# ArduinoMiniPro_Breakout.net
KiCad netlist of a schematic drawn in EAGLE
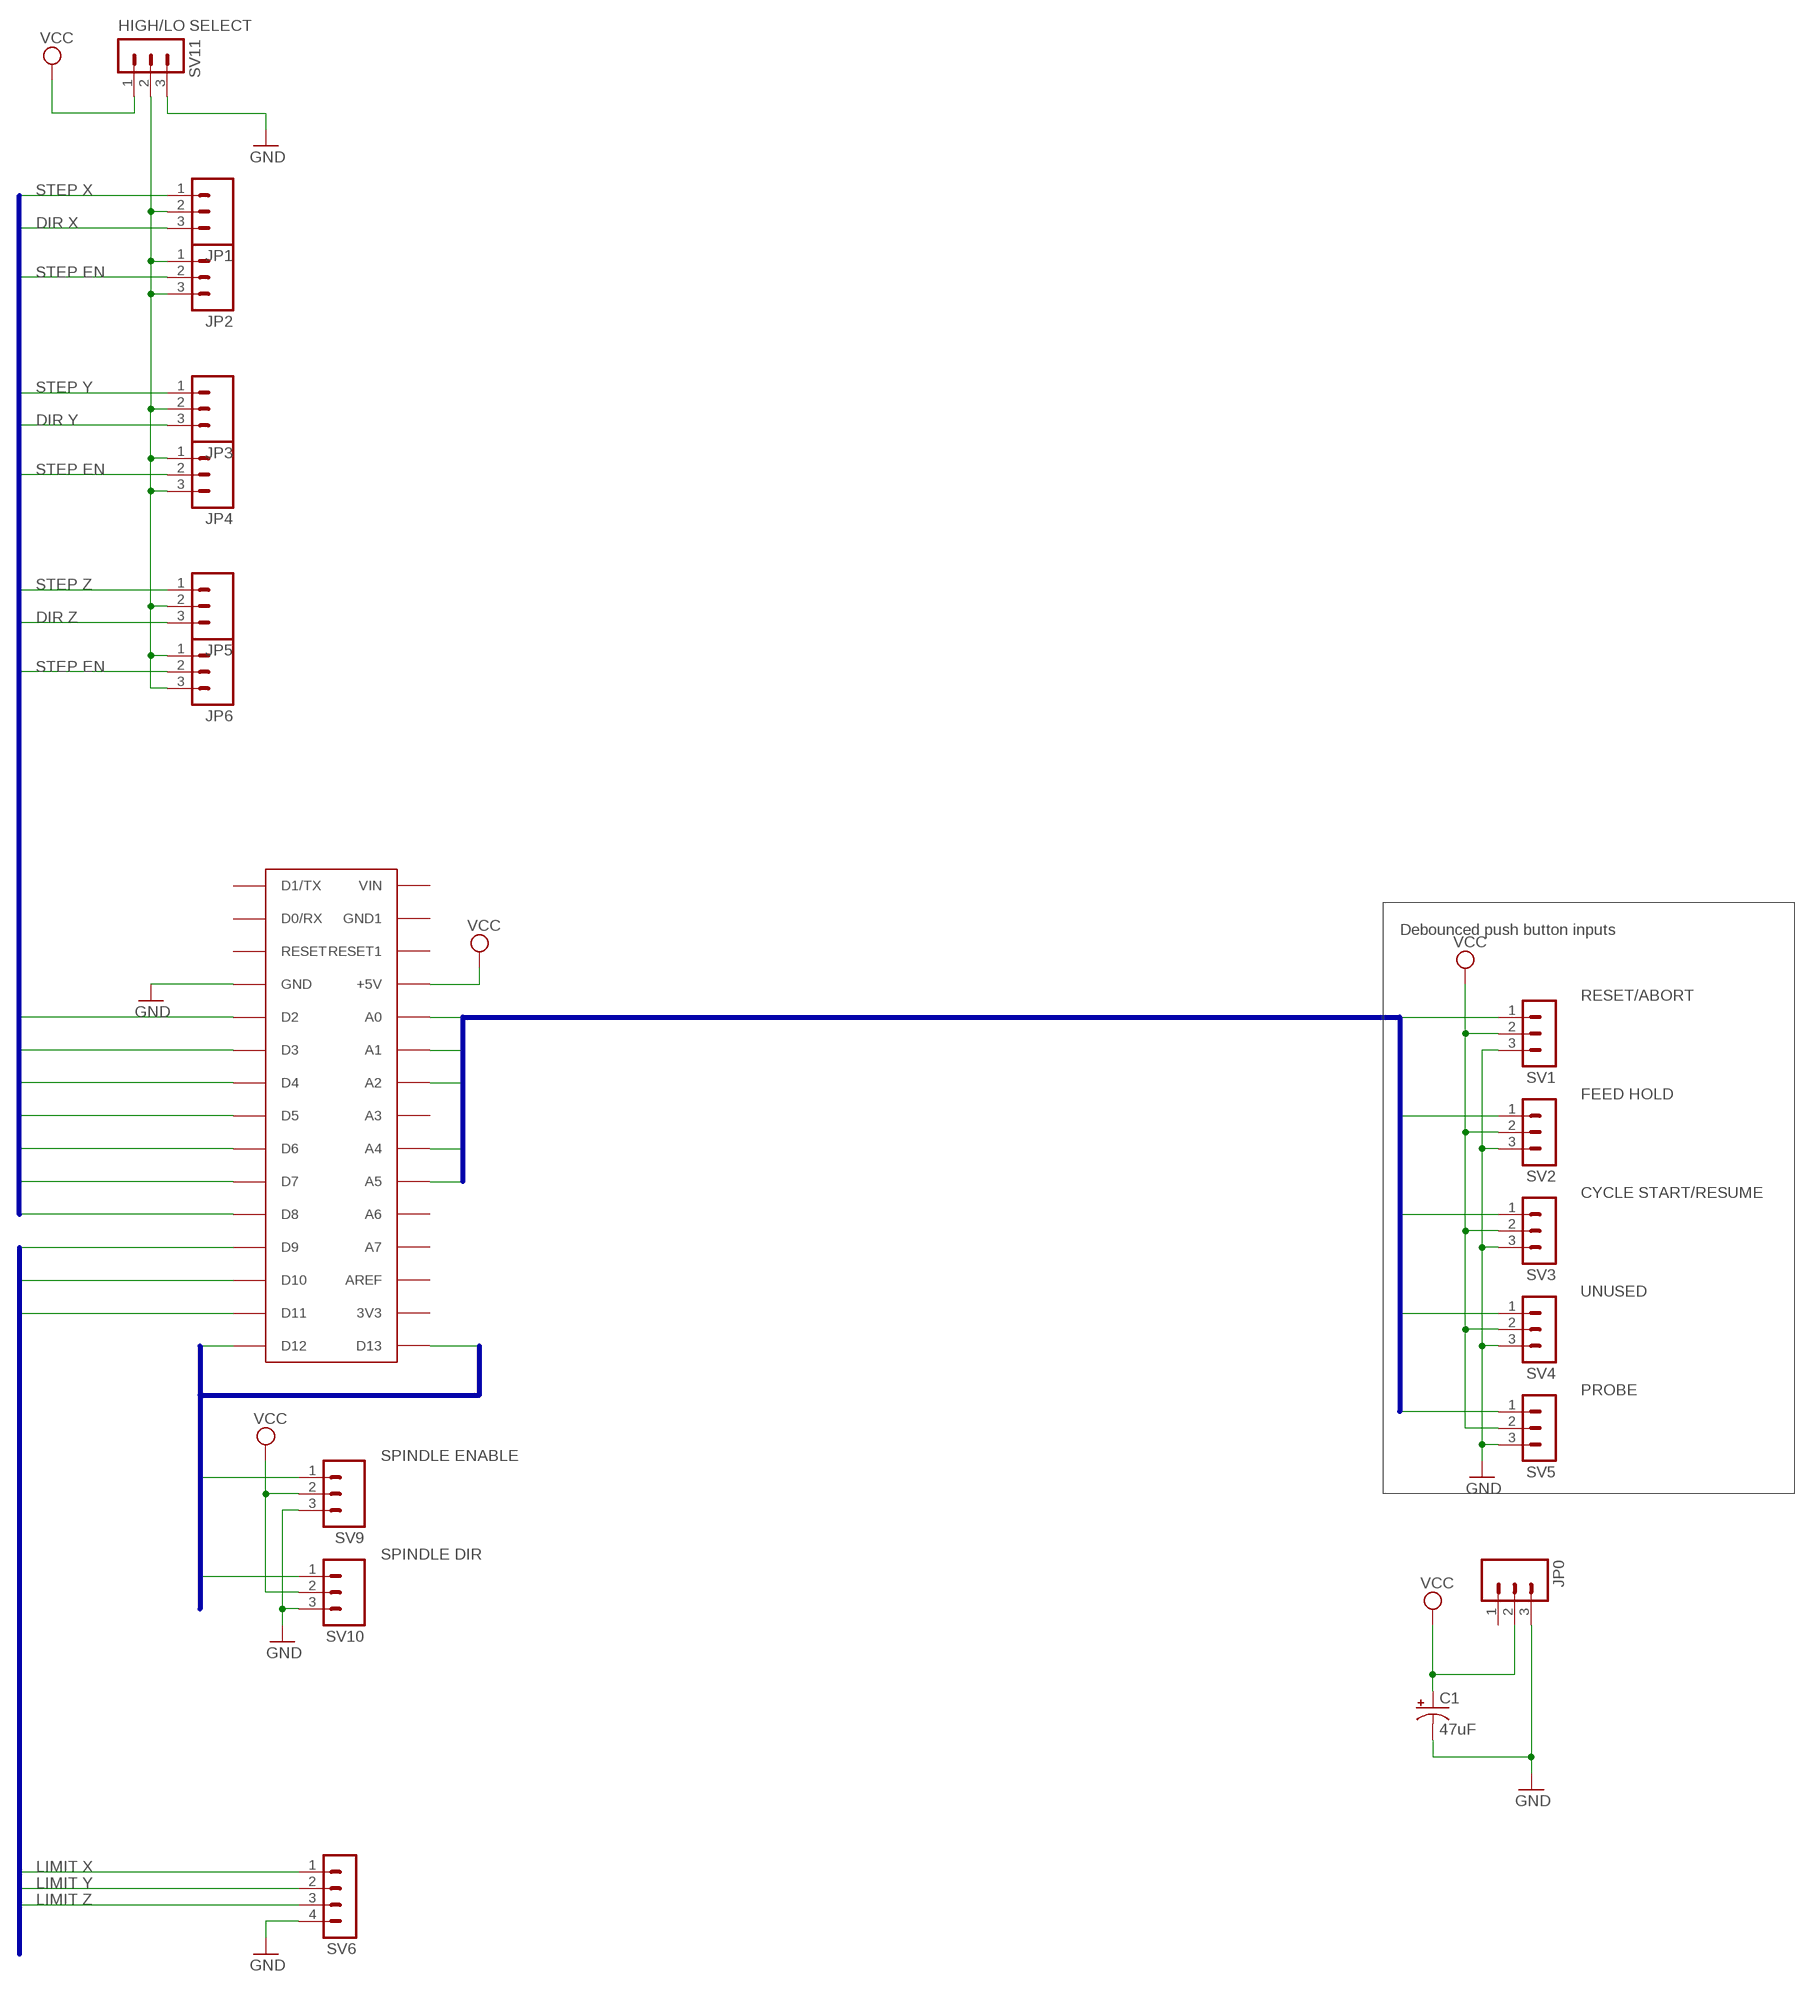
[diagram p0: schematic, sheet 1]

(export (version "E")
  (design (tool "Eeschema 10.0.6"))
  (components
    (comp (ref "C1")
      (value "47uF")
      (footprint "eagle-import:CPOL-RADIAL-10UF-25V")
      (libsource (lib "eagle-import") (part "CAP_POLPTH2"))
    )
    (comp (ref "JP0")
      (value "M03-SCREW-5MM")
      (footprint "eagle-import:SCREWTERMINAL-5MM-3")
      (libsource (lib "eagle-import") (part "M03-SCREW-5MM"))
    )
    (comp (ref "JP1")
      (value "M03-SCREW-5MM")
      (footprint "eagle-import:SCREWTERMINAL-5MM-3")
      (libsource (lib "eagle-import") (part "SparkFun-Connectors_M03-SCREW-5MM"))
    )
    (comp (ref "JP2")
      (value "M03-SCREW-5MM")
      (footprint "eagle-import:SCREWTERMINAL-5MM-3")
      (libsource (lib "eagle-import") (part "SparkFun-Connectors_M03-SCREW-5MM"))
    )
    (comp (ref "JP3")
      (value "M03-SCREW-5MM")
      (footprint "eagle-import:SCREWTERMINAL-5MM-3")
      (libsource (lib "eagle-import") (part "SparkFun-Connectors_M03-SCREW-5MM"))
    )
    (comp (ref "JP4")
      (value "M03-SCREW-5MM")
      (footprint "eagle-import:SCREWTERMINAL-5MM-3")
      (libsource (lib "eagle-import") (part "SparkFun-Connectors_M03-SCREW-5MM"))
    )
    (comp (ref "JP5")
      (value "M03-SCREW-5MM")
      (footprint "eagle-import:SCREWTERMINAL-5MM-3")
      (libsource (lib "eagle-import") (part "SparkFun-Connectors_M03-SCREW-5MM"))
    )
    (comp (ref "JP6")
      (value "M03-SCREW-5MM")
      (footprint "eagle-import:SCREWTERMINAL-5MM-3")
      (libsource (lib "eagle-import") (part "SparkFun-Connectors_M03-SCREW-5MM"))
    )
    (comp (ref "SV1")
      (value "MA03-1")
      (footprint "eagle-import:MA03-1")
      (libsource (lib "eagle-import") (part "MA03-1"))
    )
    (comp (ref "SV2")
      (value "MA03-1")
      (footprint "eagle-import:MA03-1")
      (libsource (lib "eagle-import") (part "MA03-1"))
    )
    (comp (ref "SV3")
      (value "MA03-1")
      (footprint "eagle-import:MA03-1")
      (libsource (lib "eagle-import") (part "MA03-1"))
    )
    (comp (ref "SV4")
      (value "MA03-1")
      (footprint "eagle-import:MA03-1")
      (libsource (lib "eagle-import") (part "MA03-1"))
    )
    (comp (ref "SV5")
      (value "MA03-1")
      (footprint "eagle-import:MA03-1")
      (libsource (lib "eagle-import") (part "MA03-1"))
    )
    (comp (ref "SV6")
      (value "MA04-1")
      (footprint "eagle-import:MA04-1")
      (libsource (lib "eagle-import") (part "MA04-1"))
    )
    (comp (ref "SV9")
      (value "M03-SCREW-5MM")
      (footprint "eagle-import:SCREWTERMINAL-5MM-3")
      (libsource (lib "eagle-import") (part "SparkFun-Connectors_M03-SCREW-5MM"))
    )
    (comp (ref "SV10")
      (value "M03-SCREW-5MM")
      (footprint "eagle-import:SCREWTERMINAL-5MM-3")
      (libsource (lib "eagle-import") (part "SparkFun-Connectors_M03-SCREW-5MM"))
    )
    (comp (ref "SV11")
      (value "MA03-1")
      (footprint "eagle-import:MA03-1")
      (libsource (lib "eagle-import") (part "MA03-1"))
    )
    (comp (ref "U$2")
      (value "ARDUINONANO")
      (footprint "eagle-import:PDIP-32")
      (libsource (lib "eagle-import") (part "ARDUINONANO"))
    )
  )
  (nets
    (net (code "1") (name "/B0") (class "Default")
      (node (ref "SV1") (pin "1") (pinfunction "1_1") (pintype "passive"))
      (node (ref "U$2") (pin "A0") (pinfunction "A0_A0") (pintype "bidirectional"))
    )
    (net (code "2") (name "/B1") (class "Default")
      (node (ref "SV2") (pin "1") (pinfunction "1_1") (pintype "passive"))
      (node (ref "U$2") (pin "A1") (pinfunction "A1_A1") (pintype "bidirectional"))
    )
    (net (code "3") (name "/B2") (class "Default")
      (node (ref "SV3") (pin "1") (pinfunction "1_1") (pintype "passive"))
      (node (ref "U$2") (pin "A2") (pinfunction "A2_A2") (pintype "bidirectional"))
    )
    (net (code "4") (name "/B4") (class "Default")
      (node (ref "SV4") (pin "1") (pinfunction "1_1") (pintype "passive"))
      (node (ref "U$2") (pin "A4") (pinfunction "A4_A4") (pintype "bidirectional"))
    )
    (net (code "5") (name "/B5") (class "Default")
      (node (ref "SV5") (pin "1") (pinfunction "1_1") (pintype "passive"))
      (node (ref "U$2") (pin "A5") (pinfunction "A5_A5") (pintype "bidirectional"))
    )
    (net (code "6") (name "/LIMITS0") (class "Default")
      (node (ref "SV6") (pin "1") (pinfunction "1_1") (pintype "passive"))
      (node (ref "U$2") (pin "D9") (pinfunction "D9_D9") (pintype "bidirectional"))
    )
    (net (code "7") (name "/LIMITS1") (class "Default")
      (node (ref "SV6") (pin "2") (pinfunction "2_2") (pintype "passive"))
      (node (ref "U$2") (pin "D10") (pinfunction "D10_D10") (pintype "bidirectional"))
    )
    (net (code "8") (name "/LIMITS2") (class "Default")
      (node (ref "SV6") (pin "3") (pinfunction "3_3") (pintype "passive"))
      (node (ref "U$2") (pin "D11") (pinfunction "D11_D11") (pintype "bidirectional"))
    )
    (net (code "9") (name "/SPINDLE0") (class "Default")
      (node (ref "SV9") (pin "1") (pinfunction "1_1") (pintype "passive"))
      (node (ref "U$2") (pin "D12") (pinfunction "D12_D12") (pintype "bidirectional"))
    )
    (net (code "10") (name "/SPINDLE1") (class "Default")
      (node (ref "SV10") (pin "1") (pinfunction "1_1") (pintype "passive"))
      (node (ref "U$2") (pin "D13") (pinfunction "D13_D13") (pintype "bidirectional"))
    )
    (net (code "11") (name "/STEP0") (class "Default")
      (node (ref "JP1") (pin "1") (pinfunction "1_1") (pintype "passive"))
      (node (ref "U$2") (pin "D2") (pinfunction "D2_D2") (pintype "bidirectional"))
    )
    (net (code "12") (name "/STEP1") (class "Default")
      (node (ref "JP3") (pin "1") (pinfunction "1_1") (pintype "passive"))
      (node (ref "U$2") (pin "D3") (pinfunction "D3_D3") (pintype "bidirectional"))
    )
    (net (code "13") (name "/STEP2") (class "Default")
      (node (ref "JP5") (pin "1") (pinfunction "1_1") (pintype "passive"))
      (node (ref "U$2") (pin "D4") (pinfunction "D4_D4") (pintype "bidirectional"))
    )
    (net (code "14") (name "/STEP3") (class "Default")
      (node (ref "JP1") (pin "3") (pinfunction "3_3") (pintype "passive"))
      (node (ref "U$2") (pin "D5") (pinfunction "D5_D5") (pintype "bidirectional"))
    )
    (net (code "15") (name "/STEP4") (class "Default")
      (node (ref "JP3") (pin "3") (pinfunction "3_3") (pintype "passive"))
      (node (ref "U$2") (pin "D6") (pinfunction "D6_D6") (pintype "bidirectional"))
    )
    (net (code "16") (name "/STEP5") (class "Default")
      (node (ref "JP5") (pin "3") (pinfunction "3_3") (pintype "passive"))
      (node (ref "U$2") (pin "D7") (pinfunction "D7_D7") (pintype "bidirectional"))
    )
    (net (code "17") (name "/STEP6") (class "Default")
      (node (ref "JP2") (pin "2") (pinfunction "2_2") (pintype "passive"))
      (node (ref "JP4") (pin "2") (pinfunction "2_2") (pintype "passive"))
      (node (ref "JP6") (pin "2") (pinfunction "2_2") (pintype "passive"))
      (node (ref "U$2") (pin "D8") (pinfunction "D8_D8") (pintype "bidirectional"))
    )
    (net (code "18") (name "GND") (class "Default")
      (node (ref "C1") (pin "2") (pinfunction "-_2") (pintype "passive"))
      (node (ref "JP0") (pin "3") (pinfunction "3_3") (pintype "passive"))
      (node (ref "SV1") (pin "3") (pinfunction "3_3") (pintype "passive"))
      (node (ref "SV10") (pin "3") (pinfunction "3_3") (pintype "passive"))
      (node (ref "SV11") (pin "3") (pinfunction "3_3") (pintype "passive"))
      (node (ref "SV2") (pin "3") (pinfunction "3_3") (pintype "passive"))
      (node (ref "SV3") (pin "3") (pinfunction "3_3") (pintype "passive"))
      (node (ref "SV4") (pin "3") (pinfunction "3_3") (pintype "passive"))
      (node (ref "SV5") (pin "3") (pinfunction "3_3") (pintype "passive"))
      (node (ref "SV6") (pin "4") (pinfunction "4_4") (pintype "passive"))
      (node (ref "SV9") (pin "3") (pinfunction "3_3") (pintype "passive"))
      (node (ref "U$2") (pin "GND") (pinfunction "GND_GND") (pintype "bidirectional"))
    )
    (net (code "19") (name "Net-(JP1-Pad2)") (class "Default")
      (node (ref "JP1") (pin "2") (pinfunction "2_2") (pintype "passive"))
      (node (ref "JP2") (pin "1") (pinfunction "1_1") (pintype "passive"))
      (node (ref "JP2") (pin "3") (pinfunction "3_3") (pintype "passive"))
      (node (ref "JP3") (pin "2") (pinfunction "2_2") (pintype "passive"))
      (node (ref "JP4") (pin "1") (pinfunction "1_1") (pintype "passive"))
      (node (ref "JP4") (pin "3") (pinfunction "3_3") (pintype "passive"))
      (node (ref "JP5") (pin "2") (pinfunction "2_2") (pintype "passive"))
      (node (ref "JP6") (pin "1") (pinfunction "1_1") (pintype "passive"))
      (node (ref "JP6") (pin "3") (pinfunction "3_3") (pintype "passive"))
      (node (ref "SV11") (pin "2") (pinfunction "2_2") (pintype "passive"))
    )
    (net (code "20") (name "VCC") (class "Default")
      (node (ref "C1") (pin "1") (pinfunction "+_1") (pintype "passive"))
      (node (ref "JP0") (pin "2") (pinfunction "2_2") (pintype "passive"))
      (node (ref "SV1") (pin "2") (pinfunction "2_2") (pintype "passive"))
      (node (ref "SV10") (pin "2") (pinfunction "2_2") (pintype "passive"))
      (node (ref "SV11") (pin "1") (pinfunction "1_1") (pintype "passive"))
      (node (ref "SV2") (pin "2") (pinfunction "2_2") (pintype "passive"))
      (node (ref "SV3") (pin "2") (pinfunction "2_2") (pintype "passive"))
      (node (ref "SV4") (pin "2") (pinfunction "2_2") (pintype "passive"))
      (node (ref "SV5") (pin "2") (pinfunction "2_2") (pintype "passive"))
      (node (ref "SV9") (pin "2") (pinfunction "2_2") (pintype "passive"))
      (node (ref "U$2") (pin "+5V") (pinfunction "+5V_+5V") (pintype "bidirectional"))
    )
    (net (code "21") (name "unconnected-(JP0-Pad1)") (class "Default")
      (node (ref "JP0") (pin "1") (pinfunction "1_1") (pintype "passive"))
    )
    (net (code "22") (name "unconnected-(U$2-Pad3V3)") (class "Default")
      (node (ref "U$2") (pin "3V3") (pinfunction "3V3_3V3") (pintype "bidirectional"))
    )
    (net (code "23") (name "unconnected-(U$2-PadA3)") (class "Default")
      (node (ref "U$2") (pin "A3") (pinfunction "A3_A3") (pintype "bidirectional"))
    )
    (net (code "24") (name "unconnected-(U$2-PadA6)") (class "Default")
      (node (ref "U$2") (pin "A6") (pinfunction "A6_A6") (pintype "bidirectional"))
    )
    (net (code "25") (name "unconnected-(U$2-PadA7)") (class "Default")
      (node (ref "U$2") (pin "A7") (pinfunction "A7_A7") (pintype "bidirectional"))
    )
    (net (code "26") (name "unconnected-(U$2-PadAREF)") (class "Default")
      (node (ref "U$2") (pin "AREF") (pinfunction "AREF_AREF") (pintype "bidirectional"))
    )
    (net (code "27") (name "unconnected-(U$2-PadD0{slash}RX)") (class "Default")
      (node (ref "U$2") (pin "D0/RX") (pinfunction "D0/RX_D0/RX") (pintype "bidirectional"))
    )
    (net (code "28") (name "unconnected-(U$2-PadD1{slash}TX)") (class "Default")
      (node (ref "U$2") (pin "D1/TX") (pinfunction "D1/TX_D1/TX") (pintype "bidirectional"))
    )
    (net (code "29") (name "unconnected-(U$2-PadGND1)") (class "Default")
      (node (ref "U$2") (pin "GND1") (pinfunction "GND1_GND1") (pintype "bidirectional"))
    )
    (net (code "30") (name "unconnected-(U$2-PadRESET)") (class "Default")
      (node (ref "U$2") (pin "RESET") (pinfunction "RESET_RESET") (pintype "bidirectional"))
    )
    (net (code "31") (name "unconnected-(U$2-PadRESET1)") (class "Default")
      (node (ref "U$2") (pin "RESET1") (pinfunction "RESET1_RESET1") (pintype "bidirectional"))
    )
    (net (code "32") (name "unconnected-(U$2-PadVIN)") (class "Default")
      (node (ref "U$2") (pin "VIN") (pinfunction "VIN_VIN") (pintype "bidirectional"))
    )
  )
)
